# Sheet2_3.net
KiCad netlist of a schematic drawn in Altium Designer
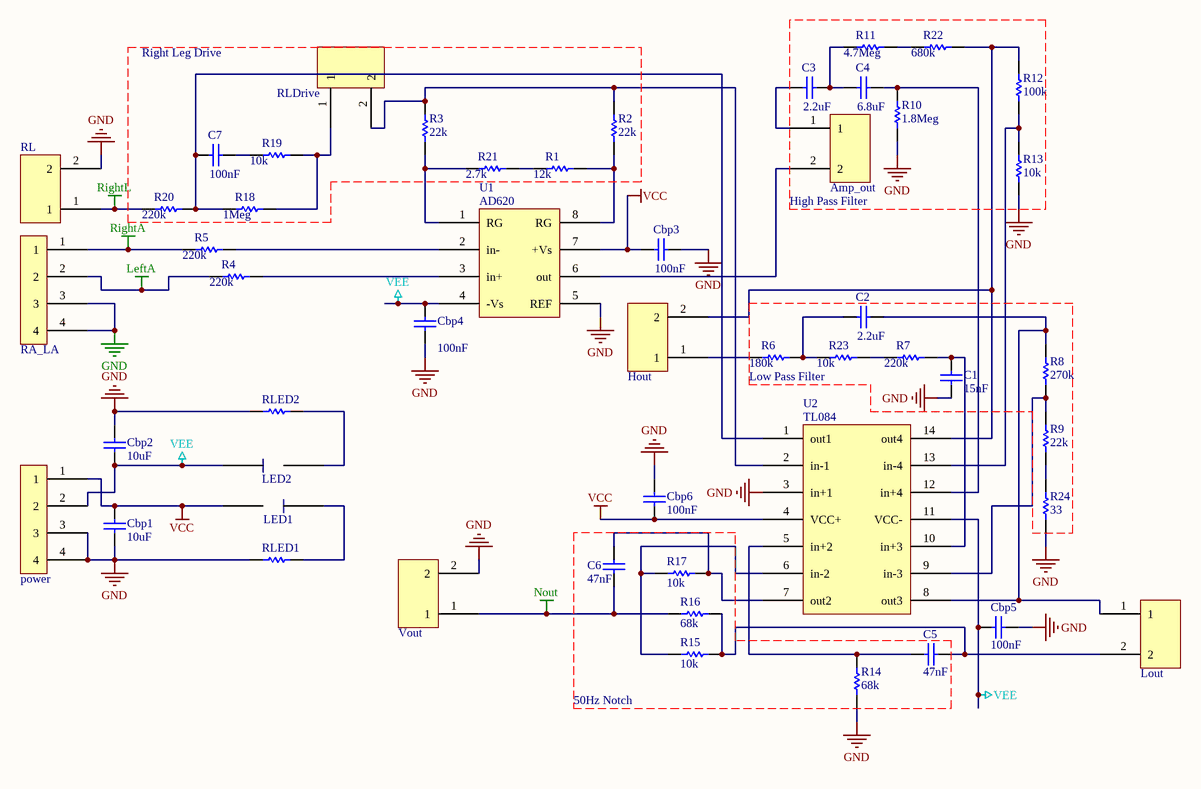
[diagram p0: Sheet2.~(3).SchDoc]

(export (version "E")
  (design (tool "Eeschema 10.0.6"))
  (components
    (comp (ref "Amp_out") (value "port") (footprint "pinheader") (libsource (lib "") (part "port_2")))
    (comp (ref "C1")
      (value "15nF")
      (footprint "cap")
      (description "Capacitor")
      (fields (field (name "Comment") "Cap") (field (name "PUBLISHER") "Altium Limited"))
      (libsource (lib "Miscellaneous Devices") (part "Cap"))
    )
    (comp (ref "C2")
      (value "2.2uF")
      (footprint "cap")
      (description "Capacitor")
      (fields (field (name "Comment") "Cap") (field (name "PUBLISHER") "Altium Limited"))
      (libsource (lib "Miscellaneous Devices") (part "Cap"))
    )
    (comp (ref "C3")
      (value "2.2uF")
      (footprint "cap")
      (description "Capacitor")
      (fields (field (name "Comment") "Cap") (field (name "PUBLISHER") "Altium Limited"))
      (libsource (lib "Miscellaneous Devices") (part "Cap"))
    )
    (comp (ref "C4")
      (value "6.8uF")
      (footprint "cap")
      (description "Capacitor")
      (fields (field (name "Comment") "Cap") (field (name "PUBLISHER") "Altium Limited"))
      (libsource (lib "Miscellaneous Devices") (part "Cap"))
    )
    (comp (ref "C5")
      (value "47nF")
      (footprint "cap")
      (description "Capacitor")
      (fields (field (name "Comment") "Cap") (field (name "PUBLISHER") "Altium Limited"))
      (libsource (lib "Miscellaneous Devices") (part "Cap"))
    )
    (comp (ref "C6")
      (value "47nF")
      (footprint "cap")
      (description "Capacitor")
      (fields (field (name "Comment") "Cap") (field (name "PUBLISHER") "Altium Limited"))
      (libsource (lib "Miscellaneous Devices") (part "Cap"))
    )
    (comp (ref "C7")
      (value "100nF")
      (footprint "cap")
      (description "Capacitor")
      (fields (field (name "Comment") "Cap") (field (name "PUBLISHER") "Altium Limited"))
      (libsource (lib "Miscellaneous Devices") (part "Cap"))
    )
    (comp (ref "Cbp1")
      (value "10uF")
      (footprint "cap")
      (description "Capacitor")
      (fields (field (name "Comment") "Cap") (field (name "PUBLISHER") "Altium Limited"))
      (libsource (lib "Miscellaneous Devices") (part "Cap"))
    )
    (comp (ref "Cbp2")
      (value "10uF")
      (footprint "cap")
      (description "Capacitor")
      (fields (field (name "Comment") "Cap") (field (name "PUBLISHER") "Altium Limited"))
      (libsource (lib "Miscellaneous Devices") (part "Cap"))
    )
    (comp (ref "Cbp3")
      (value "100nF")
      (footprint "cap")
      (description "Capacitor")
      (fields (field (name "Comment") "Cap") (field (name "PUBLISHER") "Altium Limited"))
      (libsource (lib "Miscellaneous Devices") (part "Cap"))
    )
    (comp (ref "Cbp4")
      (value "100nF")
      (footprint "cap")
      (description "Capacitor")
      (fields (field (name "Comment") "Cap") (field (name "PUBLISHER") "Altium Limited"))
      (libsource (lib "Miscellaneous Devices") (part "Cap"))
    )
    (comp (ref "Cbp5")
      (value "100nF")
      (footprint "cap")
      (description "Capacitor")
      (fields (field (name "Comment") "Cap") (field (name "PUBLISHER") "Altium Limited"))
      (libsource (lib "Miscellaneous Devices") (part "Cap"))
    )
    (comp (ref "Cbp6")
      (value "100nF")
      (footprint "cap")
      (description "Capacitor")
      (fields (field (name "Comment") "Cap") (field (name "PUBLISHER") "Altium Limited"))
      (libsource (lib "Miscellaneous Devices") (part "Cap"))
    )
    (comp (ref "Hout") (value "port") (footprint "pinheader") (libsource (lib "Schlib1") (part "port")))
    (comp (ref "LED1") (value "LED1") (footprint "LED1") (libsource (lib "Schlib1") (part "LED1")))
    (comp (ref "LED2") (value "LED1") (footprint "LED1") (libsource (lib "Schlib1") (part "LED1")))
    (comp (ref "Lout") (value "port") (footprint "pinheader") (libsource (lib "") (part "port_2")))
    (comp (ref "power") (value "pin4") (footprint "PINHEADER4") (libsource (lib "Schlib1") (part "pin4")))
    (comp (ref "R1")
      (value "12k")
      (footprint "res")
      (description "Semiconductor Resistor")
      (fields (field (name "Comment") "Res Semi") (field (name "PUBLISHER") "Altium Limited"))
      (libsource (lib "Miscellaneous Devices") (part "Res Semi"))
    )
    (comp (ref "R2")
      (value "22k")
      (footprint "res")
      (description "Semiconductor Resistor")
      (fields (field (name "Comment") "Res Semi") (field (name "PUBLISHER") "Altium Limited"))
      (libsource (lib "Miscellaneous Devices") (part "Res Semi"))
    )
    (comp (ref "R3")
      (value "22k")
      (footprint "res")
      (description "Semiconductor Resistor")
      (fields (field (name "Comment") "Res Semi") (field (name "PUBLISHER") "Altium Limited"))
      (libsource (lib "Miscellaneous Devices") (part "Res Semi"))
    )
    (comp (ref "R4")
      (value "220k")
      (footprint "res")
      (description "Semiconductor Resistor")
      (fields (field (name "Comment") "Res Semi") (field (name "PUBLISHER") "Altium Limited"))
      (libsource (lib "Miscellaneous Devices") (part "Res Semi"))
    )
    (comp (ref "R5")
      (value "220k")
      (footprint "res")
      (description "Semiconductor Resistor")
      (fields (field (name "Comment") "Res Semi") (field (name "PUBLISHER") "Altium Limited"))
      (libsource (lib "Miscellaneous Devices") (part "Res Semi"))
    )
    (comp (ref "R6")
      (value "180k")
      (footprint "res")
      (description "Semiconductor Resistor")
      (fields (field (name "Comment") "Res Semi") (field (name "PUBLISHER") "Altium Limited"))
      (libsource (lib "Miscellaneous Devices") (part "Res Semi"))
    )
    (comp (ref "R7")
      (value "220k")
      (footprint "res")
      (description "Semiconductor Resistor")
      (fields (field (name "Comment") "Res Semi") (field (name "PUBLISHER") "Altium Limited"))
      (libsource (lib "Miscellaneous Devices") (part "Res Semi"))
    )
    (comp (ref "R8")
      (value "270k")
      (footprint "res")
      (description "Semiconductor Resistor")
      (fields (field (name "Comment") "Res Semi") (field (name "PUBLISHER") "Altium Limited"))
      (libsource (lib "Miscellaneous Devices") (part "Res Semi"))
    )
    (comp (ref "R9")
      (value "22k")
      (footprint "res")
      (description "Semiconductor Resistor")
      (fields (field (name "Comment") "Res Semi") (field (name "PUBLISHER") "Altium Limited"))
      (libsource (lib "Miscellaneous Devices") (part "Res Semi"))
    )
    (comp (ref "R10")
      (value "1.8Meg")
      (footprint "res")
      (description "Semiconductor Resistor")
      (fields (field (name "Comment") "Res Semi") (field (name "PUBLISHER") "Altium Limited"))
      (libsource (lib "Miscellaneous Devices") (part "Res Semi"))
    )
    (comp (ref "R11")
      (value "4.7Meg")
      (footprint "res")
      (description "Semiconductor Resistor")
      (fields (field (name "Comment") "Res Semi") (field (name "PUBLISHER") "Altium Limited"))
      (libsource (lib "Miscellaneous Devices") (part "Res Semi"))
    )
    (comp (ref "R12")
      (value "100k")
      (footprint "res")
      (description "Semiconductor Resistor")
      (fields (field (name "Comment") "Res Semi") (field (name "PUBLISHER") "Altium Limited"))
      (libsource (lib "Miscellaneous Devices") (part "Res Semi"))
    )
    (comp (ref "R13")
      (value "10k")
      (footprint "res")
      (description "Semiconductor Resistor")
      (fields (field (name "Comment") "Res Semi") (field (name "PUBLISHER") "Altium Limited"))
      (libsource (lib "Miscellaneous Devices") (part "Res Semi"))
    )
    (comp (ref "R14")
      (value "68k")
      (footprint "res")
      (description "Semiconductor Resistor")
      (fields (field (name "Comment") "Res Semi") (field (name "PUBLISHER") "Altium Limited"))
      (libsource (lib "Miscellaneous Devices") (part "Res Semi"))
    )
    (comp (ref "R15")
      (value "10k")
      (footprint "res")
      (description "Semiconductor Resistor")
      (fields (field (name "Comment") "Res Semi") (field (name "PUBLISHER") "Altium Limited"))
      (libsource (lib "Miscellaneous Devices") (part "Res Semi"))
    )
    (comp (ref "R16")
      (value "68k")
      (footprint "res")
      (description "Semiconductor Resistor")
      (fields (field (name "Comment") "Res Semi") (field (name "PUBLISHER") "Altium Limited"))
      (libsource (lib "Miscellaneous Devices") (part "Res Semi"))
    )
    (comp (ref "R17")
      (value "10k")
      (footprint "res")
      (description "Semiconductor Resistor")
      (fields (field (name "Comment") "Res Semi") (field (name "PUBLISHER") "Altium Limited"))
      (libsource (lib "Miscellaneous Devices") (part "Res Semi"))
    )
    (comp (ref "R18")
      (value "1Meg")
      (footprint "res")
      (description "Semiconductor Resistor")
      (fields (field (name "Comment") "Res Semi") (field (name "PUBLISHER") "Altium Limited"))
      (libsource (lib "Miscellaneous Devices") (part "Res Semi"))
    )
    (comp (ref "R19")
      (value "10k")
      (footprint "res")
      (description "Semiconductor Resistor")
      (fields (field (name "Comment") "Res Semi") (field (name "PUBLISHER") "Altium Limited"))
      (libsource (lib "Miscellaneous Devices") (part "Res Semi"))
    )
    (comp (ref "R20")
      (value "220k")
      (footprint "res")
      (description "Semiconductor Resistor")
      (fields (field (name "Comment") "Res Semi") (field (name "PUBLISHER") "Altium Limited"))
      (libsource (lib "Miscellaneous Devices") (part "Res Semi"))
    )
    (comp (ref "R21")
      (value "2.7k")
      (footprint "res")
      (description "Semiconductor Resistor")
      (fields (field (name "Comment") "Res Semi") (field (name "PUBLISHER") "Altium Limited"))
      (libsource (lib "Miscellaneous Devices") (part "Res Semi"))
    )
    (comp (ref "R22")
      (value "680k")
      (footprint "res")
      (description "Semiconductor Resistor")
      (fields (field (name "Comment") "Res Semi") (field (name "PUBLISHER") "Altium Limited"))
      (libsource (lib "Miscellaneous Devices") (part "Res Semi"))
    )
    (comp (ref "R23")
      (value "10k")
      (footprint "res")
      (description "Semiconductor Resistor")
      (fields (field (name "Comment") "Res Semi") (field (name "PUBLISHER") "Altium Limited"))
      (libsource (lib "Miscellaneous Devices") (part "Res Semi"))
    )
    (comp (ref "R24")
      (value "33")
      (footprint "res")
      (description "Semiconductor Resistor")
      (fields (field (name "Comment") "Res Semi") (field (name "PUBLISHER") "Altium Limited"))
      (libsource (lib "Miscellaneous Devices") (part "Res Semi"))
    )
    (comp (ref "RA_LA") (value "pin4") (footprint "PINHEADER4") (libsource (lib "Schlib1") (part "pin4")))
    (comp (ref "RL") (value "port") (footprint "pinheader") (libsource (lib "Schlib1") (part "port")))
    (comp (ref "RLDrive") (value "port") (footprint "pinheader") (libsource (lib "") (part "port_1")))
    (comp (ref "RLED1")
      (value "Res Semi")
      (footprint "res")
      (description "Semiconductor Resistor")
      (fields (field (name "PUBLISHER") "Altium Limited"))
      (libsource (lib "Miscellaneous Devices") (part "Res Semi"))
    )
    (comp (ref "RLED2")
      (value "Res Semi")
      (footprint "res")
      (description "Semiconductor Resistor")
      (fields (field (name "PUBLISHER") "Altium Limited"))
      (libsource (lib "Miscellaneous Devices") (part "Res Semi"))
    )
    (comp (ref "U1") (value "AD620") (footprint "AD620") (libsource (lib "Schlib1") (part "AD620")))
    (comp (ref "U2") (value "TL084") (footprint "TL084") (libsource (lib "Schlib1") (part "TL084")))
    (comp (ref "Vout") (value "port") (footprint "pinheader") (libsource (lib "Schlib1") (part "port")))
  )
  (nets
    (net (code "1") (name "GND") (class "Default")
      (node (ref "C1") (pin "1") (pinfunction "1_1") (pintype "passive"))
      (node (ref "Cbp1") (pin "1") (pinfunction "1_1") (pintype "passive"))
      (node (ref "Cbp2") (pin "2") (pinfunction "2_2") (pintype "passive"))
      (node (ref "Cbp3") (pin "2") (pinfunction "2_2") (pintype "passive"))
      (node (ref "Cbp4") (pin "1") (pinfunction "1_1") (pintype "passive"))
      (node (ref "Cbp5") (pin "1") (pinfunction "1_1") (pintype "passive"))
      (node (ref "Cbp6") (pin "1") (pinfunction "1_1") (pintype "passive"))
      (node (ref "R10") (pin "1") (pinfunction "1_1") (pintype "passive"))
      (node (ref "R13") (pin "1") (pinfunction "1_1") (pintype "passive"))
      (node (ref "R14") (pin "1") (pinfunction "1_1") (pintype "passive"))
      (node (ref "R24") (pin "1") (pinfunction "1_1") (pintype "passive"))
      (node (ref "RA_LA") (pin "3") (pinfunction "3_3") (pintype "passive"))
      (node (ref "RA_LA") (pin "4") (pinfunction "4_4") (pintype "passive"))
      (node (ref "RL") (pin "2") (pinfunction "2_2") (pintype "passive"))
      (node (ref "RLED1") (pin "1") (pinfunction "1_1") (pintype "passive"))
      (node (ref "RLED2") (pin "1") (pinfunction "1_1") (pintype "passive"))
      (node (ref "U1") (pin "5") (pinfunction "REF_5") (pintype "passive"))
      (node (ref "U2") (pin "3") (pinfunction "in+1_3") (pintype "passive"))
      (node (ref "Vout") (pin "2") (pinfunction "2_2") (pintype "passive"))
      (node (ref "power") (pin "3") (pinfunction "3_3") (pintype "passive"))
      (node (ref "power") (pin "4") (pinfunction "4_4") (pintype "passive"))
    )
    (net (code "2") (name "LeftA") (class "Default")
      (node (ref "R4") (pin "1") (pinfunction "1_1") (pintype "passive"))
      (node (ref "RA_LA") (pin "2") (pinfunction "2_2") (pintype "passive"))
    )
    (net (code "3") (name "Net-(Amp_out-Pad1)") (class "Default")
      (node (ref "Amp_out") (pin "1") (pinfunction "1_1") (pintype "passive"))
      (node (ref "C3") (pin "1") (pinfunction "1_1") (pintype "passive"))
    )
    (net (code "4") (name "Net-(C2-Pad1)") (class "Default")
      (node (ref "C2") (pin "1") (pinfunction "1_1") (pintype "passive"))
      (node (ref "R23") (pin "1") (pinfunction "1_1") (pintype "passive"))
      (node (ref "R6") (pin "2") (pinfunction "2_2") (pintype "passive"))
    )
    (net (code "5") (name "Net-(C3-Pad2)") (class "Default")
      (node (ref "C3") (pin "2") (pinfunction "2_2") (pintype "passive"))
      (node (ref "C4") (pin "1") (pinfunction "1_1") (pintype "passive"))
      (node (ref "R11") (pin "1") (pinfunction "1_1") (pintype "passive"))
    )
    (net (code "6") (name "Net-(C5-Pad1)") (class "Default")
      (node (ref "C5") (pin "1") (pinfunction "1_1") (pintype "passive"))
      (node (ref "Lout") (pin "2") (pinfunction "2_2") (pintype "passive"))
      (node (ref "R15") (pin "2") (pinfunction "2_2") (pintype "passive"))
      (node (ref "R16") (pin "2") (pinfunction "2_2") (pintype "passive"))
    )
    (net (code "7") (name "Net-(C7-Pad2)") (class "Default")
      (node (ref "C7") (pin "2") (pinfunction "2_2") (pintype "passive"))
      (node (ref "R19") (pin "1") (pinfunction "1_1") (pintype "passive"))
    )
    (net (code "8") (name "Net-(Hout-Pad1)") (class "Default")
      (node (ref "Hout") (pin "1") (pinfunction "1_1") (pintype "passive"))
      (node (ref "R6") (pin "1") (pinfunction "1_1") (pintype "passive"))
    )
    (net (code "9") (name "Net-(LED1-kathod)") (class "Default")
      (node (ref "LED1") (pin "1") (pinfunction "kathod_1") (pintype "passive"))
      (node (ref "RLED1") (pin "2") (pinfunction "2_2") (pintype "passive"))
    )
    (net (code "10") (name "Net-(LED2-Anode)") (class "Default")
      (node (ref "LED2") (pin "2") (pinfunction "Anode_2") (pintype "passive"))
      (node (ref "RLED2") (pin "2") (pinfunction "2_2") (pintype "passive"))
    )
    (net (code "11") (name "Net-(R1-Pad1)") (class "Default")
      (node (ref "R1") (pin "1") (pinfunction "1_1") (pintype "passive"))
      (node (ref "R21") (pin "2") (pinfunction "2_2") (pintype "passive"))
    )
    (net (code "12") (name "Net-(R1-Pad2)") (class "Default")
      (node (ref "R1") (pin "2") (pinfunction "2_2") (pintype "passive"))
      (node (ref "R2") (pin "1") (pinfunction "1_1") (pintype "passive"))
      (node (ref "U1") (pin "8") (pinfunction "RG_8") (pintype "passive"))
    )
    (net (code "13") (name "Net-(R11-Pad2)") (class "Default")
      (node (ref "R11") (pin "2") (pinfunction "2_2") (pintype "passive"))
      (node (ref "R22") (pin "1") (pinfunction "1_1") (pintype "passive"))
    )
    (net (code "14") (name "Net-(R18-Pad2)") (class "Default")
      (node (ref "R18") (pin "2") (pinfunction "2_2") (pintype "passive"))
      (node (ref "R19") (pin "2") (pinfunction "2_2") (pintype "passive"))
      (node (ref "RLDrive") (pin "1") (pinfunction "1_1") (pintype "passive"))
    )
    (net (code "15") (name "Net-(R21-Pad1)") (class "Default")
      (node (ref "R21") (pin "1") (pinfunction "1_1") (pintype "passive"))
      (node (ref "R3") (pin "2") (pinfunction "2_2") (pintype "passive"))
      (node (ref "U1") (pin "1") (pinfunction "RG_1") (pintype "passive"))
    )
    (net (code "16") (name "Net-(R23-Pad2)") (class "Default")
      (node (ref "R23") (pin "2") (pinfunction "2_2") (pintype "passive"))
      (node (ref "R7") (pin "1") (pinfunction "1_1") (pintype "passive"))
    )
    (net (code "17") (name "Net-(R24-Pad2)") (class "Default")
      (node (ref "R24") (pin "2") (pinfunction "2_2") (pintype "passive"))
      (node (ref "R9") (pin "1") (pinfunction "1_1") (pintype "passive"))
    )
    (net (code "18") (name "Net-(U1-in+)") (class "Default")
      (node (ref "R4") (pin "2") (pinfunction "2_2") (pintype "passive"))
      (node (ref "U1") (pin "3") (pinfunction "in+_3") (pintype "passive"))
    )
    (net (code "19") (name "Net-(U1-in-)") (class "Default")
      (node (ref "R5") (pin "2") (pinfunction "2_2") (pintype "passive"))
      (node (ref "U1") (pin "2") (pinfunction "in-_2") (pintype "passive"))
    )
    (net (code "20") (name "Net-(U1-out)") (class "Default")
      (node (ref "Amp_out") (pin "2") (pinfunction "2_2") (pintype "passive"))
      (node (ref "U1") (pin "6") (pinfunction "out_6") (pintype "passive"))
    )
    (net (code "21") (name "Net-(U2-in+2)") (class "Default")
      (node (ref "C5") (pin "2") (pinfunction "2_2") (pintype "passive"))
      (node (ref "R14") (pin "2") (pinfunction "2_2") (pintype "passive"))
      (node (ref "U2") (pin "5") (pinfunction "in+2_5") (pintype "passive"))
    )
    (net (code "22") (name "Net-(U2-in+3)") (class "Default")
      (node (ref "C1") (pin "2") (pinfunction "2_2") (pintype "passive"))
      (node (ref "R7") (pin "2") (pinfunction "2_2") (pintype "passive"))
      (node (ref "U2") (pin "10") (pinfunction "in+3_10") (pintype "passive"))
    )
    (net (code "23") (name "Net-(U2-in+4)") (class "Default")
      (node (ref "C4") (pin "2") (pinfunction "2_2") (pintype "passive"))
      (node (ref "R10") (pin "2") (pinfunction "2_2") (pintype "passive"))
      (node (ref "U2") (pin "12") (pinfunction "in+4_12") (pintype "passive"))
    )
    (net (code "24") (name "Net-(U2-in-1)") (class "Default")
      (node (ref "R2") (pin "2") (pinfunction "2_2") (pintype "passive"))
      (node (ref "R3") (pin "1") (pinfunction "1_1") (pintype "passive"))
      (node (ref "RLDrive") (pin "2") (pinfunction "2_2") (pintype "passive"))
      (node (ref "U2") (pin "2") (pinfunction "in-1_2") (pintype "passive"))
    )
    (net (code "25") (name "Net-(U2-in-2)") (class "Default")
      (node (ref "R15") (pin "1") (pinfunction "1_1") (pintype "passive"))
      (node (ref "R17") (pin "1") (pinfunction "1_1") (pintype "passive"))
      (node (ref "U2") (pin "6") (pinfunction "in-2_6") (pintype "passive"))
    )
    (net (code "26") (name "Net-(U2-in-3)") (class "Default")
      (node (ref "R8") (pin "1") (pinfunction "1_1") (pintype "passive"))
      (node (ref "R9") (pin "2") (pinfunction "2_2") (pintype "passive"))
      (node (ref "U2") (pin "9") (pinfunction "in-3_9") (pintype "passive"))
    )
    (net (code "27") (name "Net-(U2-in-4)") (class "Default")
      (node (ref "R12") (pin "1") (pinfunction "1_1") (pintype "passive"))
      (node (ref "R13") (pin "2") (pinfunction "2_2") (pintype "passive"))
      (node (ref "U2") (pin "13") (pinfunction "in-4_13") (pintype "passive"))
    )
    (net (code "28") (name "Net-(U2-out1)") (class "Default")
      (node (ref "C7") (pin "1") (pinfunction "1_1") (pintype "passive"))
      (node (ref "R18") (pin "1") (pinfunction "1_1") (pintype "passive"))
      (node (ref "R20") (pin "2") (pinfunction "2_2") (pintype "passive"))
      (node (ref "U2") (pin "1") (pinfunction "out1_1") (pintype "passive"))
    )
    (net (code "29") (name "Net-(U2-out2)") (class "Default")
      (node (ref "C6") (pin "2") (pinfunction "2_2") (pintype "passive"))
      (node (ref "R17") (pin "2") (pinfunction "2_2") (pintype "passive"))
      (node (ref "U2") (pin "7") (pinfunction "out2_7") (pintype "passive"))
    )
    (net (code "30") (name "Net-(U2-out3)") (class "Default")
      (node (ref "C2") (pin "2") (pinfunction "2_2") (pintype "passive"))
      (node (ref "Lout") (pin "1") (pinfunction "1_1") (pintype "passive"))
      (node (ref "R8") (pin "2") (pinfunction "2_2") (pintype "passive"))
      (node (ref "U2") (pin "8") (pinfunction "out3_8") (pintype "passive"))
    )
    (net (code "31") (name "Net-(U2-out4)") (class "Default")
      (node (ref "Hout") (pin "2") (pinfunction "2_2") (pintype "passive"))
      (node (ref "R12") (pin "2") (pinfunction "2_2") (pintype "passive"))
      (node (ref "R22") (pin "2") (pinfunction "2_2") (pintype "passive"))
      (node (ref "U2") (pin "14") (pinfunction "out4_14") (pintype "passive"))
    )
    (net (code "32") (name "Nout") (class "Default")
      (node (ref "C6") (pin "1") (pinfunction "1_1") (pintype "passive"))
      (node (ref "R16") (pin "1") (pinfunction "1_1") (pintype "passive"))
      (node (ref "Vout") (pin "1") (pinfunction "1_1") (pintype "passive"))
    )
    (net (code "33") (name "RightA") (class "Default")
      (node (ref "R5") (pin "1") (pinfunction "1_1") (pintype "passive"))
      (node (ref "RA_LA") (pin "1") (pinfunction "1_1") (pintype "passive"))
    )
    (net (code "34") (name "RightL") (class "Default")
      (node (ref "R20") (pin "1") (pinfunction "1_1") (pintype "passive"))
      (node (ref "RL") (pin "1") (pinfunction "1_1") (pintype "passive"))
    )
    (net (code "35") (name "VCC") (class "Default")
      (node (ref "Cbp1") (pin "2") (pinfunction "2_2") (pintype "passive"))
      (node (ref "Cbp3") (pin "1") (pinfunction "1_1") (pintype "passive"))
      (node (ref "Cbp6") (pin "2") (pinfunction "2_2") (pintype "passive"))
      (node (ref "LED1") (pin "2") (pinfunction "Anode_2") (pintype "passive"))
      (node (ref "U1") (pin "7") (pinfunction "+Vs_7") (pintype "passive"))
      (node (ref "U2") (pin "4") (pinfunction "VCC+_4") (pintype "passive"))
      (node (ref "power") (pin "1") (pinfunction "1_1") (pintype "passive"))
    )
    (net (code "36") (name "VEE") (class "Default")
      (node (ref "Cbp2") (pin "1") (pinfunction "1_1") (pintype "passive"))
      (node (ref "Cbp4") (pin "2") (pinfunction "2_2") (pintype "passive"))
      (node (ref "Cbp5") (pin "2") (pinfunction "2_2") (pintype "passive"))
      (node (ref "LED2") (pin "1") (pinfunction "kathod_1") (pintype "passive"))
      (node (ref "U1") (pin "4") (pinfunction "-Vs_4") (pintype "passive"))
      (node (ref "U2") (pin "11") (pinfunction "VCC-_11") (pintype "passive"))
      (node (ref "power") (pin "2") (pinfunction "2_2") (pintype "passive"))
    )
  )
)
